# Adafruit_NeoPixel_Ring_24_B_-_Holder_4.net
KiCad netlist of a schematic drawn in EAGLE
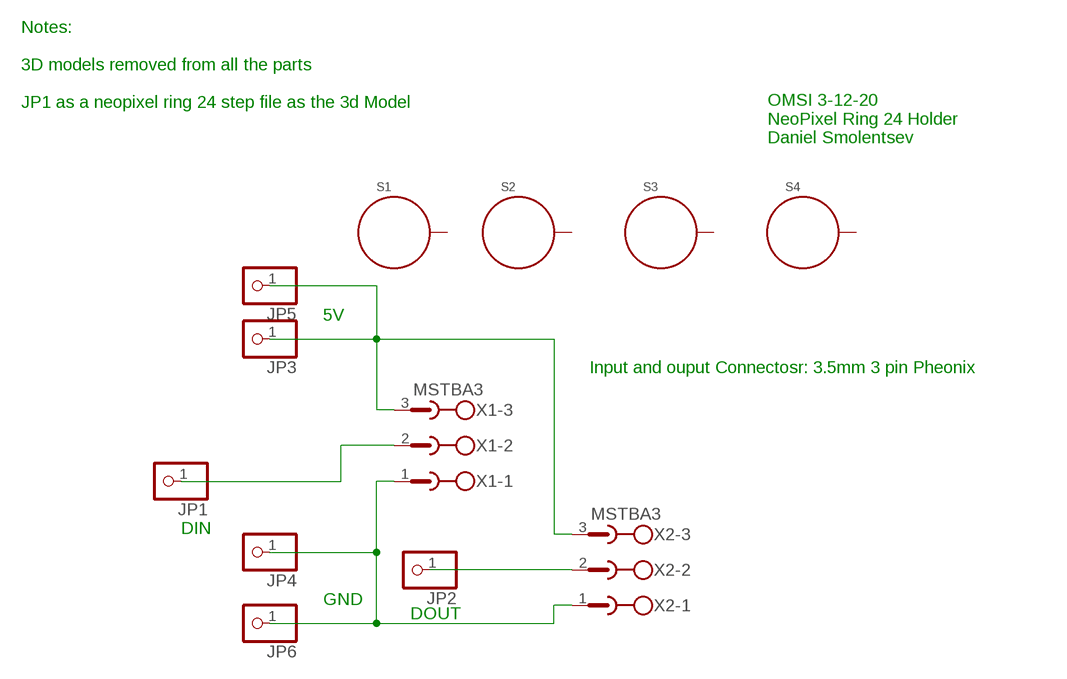
[diagram p0: schematic, sheet 1]

(export (version "E")
  (design (tool "Eeschema 10.0.6"))
  (components
    (comp (ref "JP1")
      (value "PINHD-1X1CB")
      (footprint "eagle-import:1X01-CLEANBIG")
      (libsource (lib "eagle-import") (part "PINHD-1X1CB"))
    )
    (comp (ref "JP2")
      (value "PINHD-1X1CB")
      (footprint "eagle-import:1X01-CLEANBIG")
      (libsource (lib "eagle-import") (part "PINHD-1X1CB"))
    )
    (comp (ref "JP3")
      (value "PINHD-1X1CB")
      (footprint "eagle-import:1X01-CLEANBIG")
      (libsource (lib "eagle-import") (part "PINHD-1X1CB"))
    )
    (comp (ref "JP4")
      (value "PINHD-1X1CB")
      (footprint "eagle-import:1X01-CLEANBIG")
      (libsource (lib "eagle-import") (part "PINHD-1X1CB"))
    )
    (comp (ref "JP5")
      (value "PINHD-1X1CB")
      (footprint "eagle-import:1X01-CLEANBIG")
      (libsource (lib "eagle-import") (part "PINHD-1X1CB"))
    )
    (comp (ref "JP6")
      (value "PINHD-1X1CB")
      (footprint "eagle-import:1X01-CLEANBIG")
      (libsource (lib "eagle-import") (part "PINHD-1X1CB"))
    )
    (comp (ref "S1")
      (value "STANDOFF_ELECTRICAL.17\"")
      (footprint "eagle-import:STANDOFF-ELECTRICAL")
      (libsource (lib "eagle-import") (part "STANDOFF_ELECTRICAL.17{dblquote}"))
    )
    (comp (ref "S2")
      (value "STANDOFF_ELECTRICAL.17\"")
      (footprint "eagle-import:STANDOFF-ELECTRICAL")
      (libsource (lib "eagle-import") (part "STANDOFF_ELECTRICAL.17{dblquote}"))
    )
    (comp (ref "S3")
      (value "STANDOFF_ELECTRICAL.17\"")
      (footprint "eagle-import:STANDOFF-ELECTRICAL")
      (libsource (lib "eagle-import") (part "STANDOFF_ELECTRICAL.17{dblquote}"))
    )
    (comp (ref "S4")
      (value "STANDOFF_ELECTRICAL.17\"")
      (footprint "eagle-import:STANDOFF-ELECTRICAL")
      (libsource (lib "eagle-import") (part "STANDOFF_ELECTRICAL.17{dblquote}"))
    )
    (comp (ref "X1")
      (value "MSTBA3")
      (footprint "eagle-import:MSTBA3")
      (fields (field (name "MF") "FARNELL") (field (name "MPN") "1757255"))
      (libsource (lib "eagle-import") (part "MSTBA3"))
    )
    (comp (ref "X2")
      (value "MSTBA3")
      (footprint "eagle-import:MSTBA3")
      (fields (field (name "MF") "FARNELL") (field (name "MPN") "1757255"))
      (libsource (lib "eagle-import") (part "MSTBA3"))
    )
  )
  (nets
    (net (code "1") (name "Net-(JP4-Pad1)") (class "Default")
      (node (ref "JP4") (pin "1") (pinfunction "1_1") (pintype "passive"))
      (node (ref "JP6") (pin "1") (pinfunction "1_1") (pintype "passive"))
      (node (ref "X1") (pin "1") (pinfunction "1_1") (pintype "passive"))
      (node (ref "X2") (pin "1") (pinfunction "1_1") (pintype "passive"))
    )
    (net (code "2") (name "Net-(X1B-1)") (class "Default")
      (node (ref "JP1") (pin "1") (pinfunction "1_1") (pintype "passive"))
      (node (ref "X1") (pin "2") (pinfunction "1_2") (pintype "passive"))
    )
    (net (code "3") (name "Net-(X1C-1)") (class "Default")
      (node (ref "JP3") (pin "1") (pinfunction "1_1") (pintype "passive"))
      (node (ref "JP5") (pin "1") (pinfunction "1_1") (pintype "passive"))
      (node (ref "X1") (pin "3") (pinfunction "1_3") (pintype "passive"))
      (node (ref "X2") (pin "3") (pinfunction "1_3") (pintype "passive"))
    )
    (net (code "4") (name "Net-(X2B-1)") (class "Default")
      (node (ref "JP2") (pin "1") (pinfunction "1_1") (pintype "passive"))
      (node (ref "X2") (pin "2") (pinfunction "1_2") (pintype "passive"))
    )
    (net (code "5") (name "unconnected-(S1-P$1-PadP1)") (class "Default")
      (node (ref "S1") (pin "P1") (pinfunction "P$1_P1") (pintype "bidirectional"))
    )
    (net (code "6") (name "unconnected-(S2-P$1-PadP1)") (class "Default")
      (node (ref "S2") (pin "P1") (pinfunction "P$1_P1") (pintype "bidirectional"))
    )
    (net (code "7") (name "unconnected-(S3-P$1-PadP1)") (class "Default")
      (node (ref "S3") (pin "P1") (pinfunction "P$1_P1") (pintype "bidirectional"))
    )
    (net (code "8") (name "unconnected-(S4-P$1-PadP1)") (class "Default")
      (node (ref "S4") (pin "P1") (pinfunction "P$1_P1") (pintype "bidirectional"))
    )
  )
)
